# TMC2130.net
KiCad netlist of a schematic drawn in Altium Designer
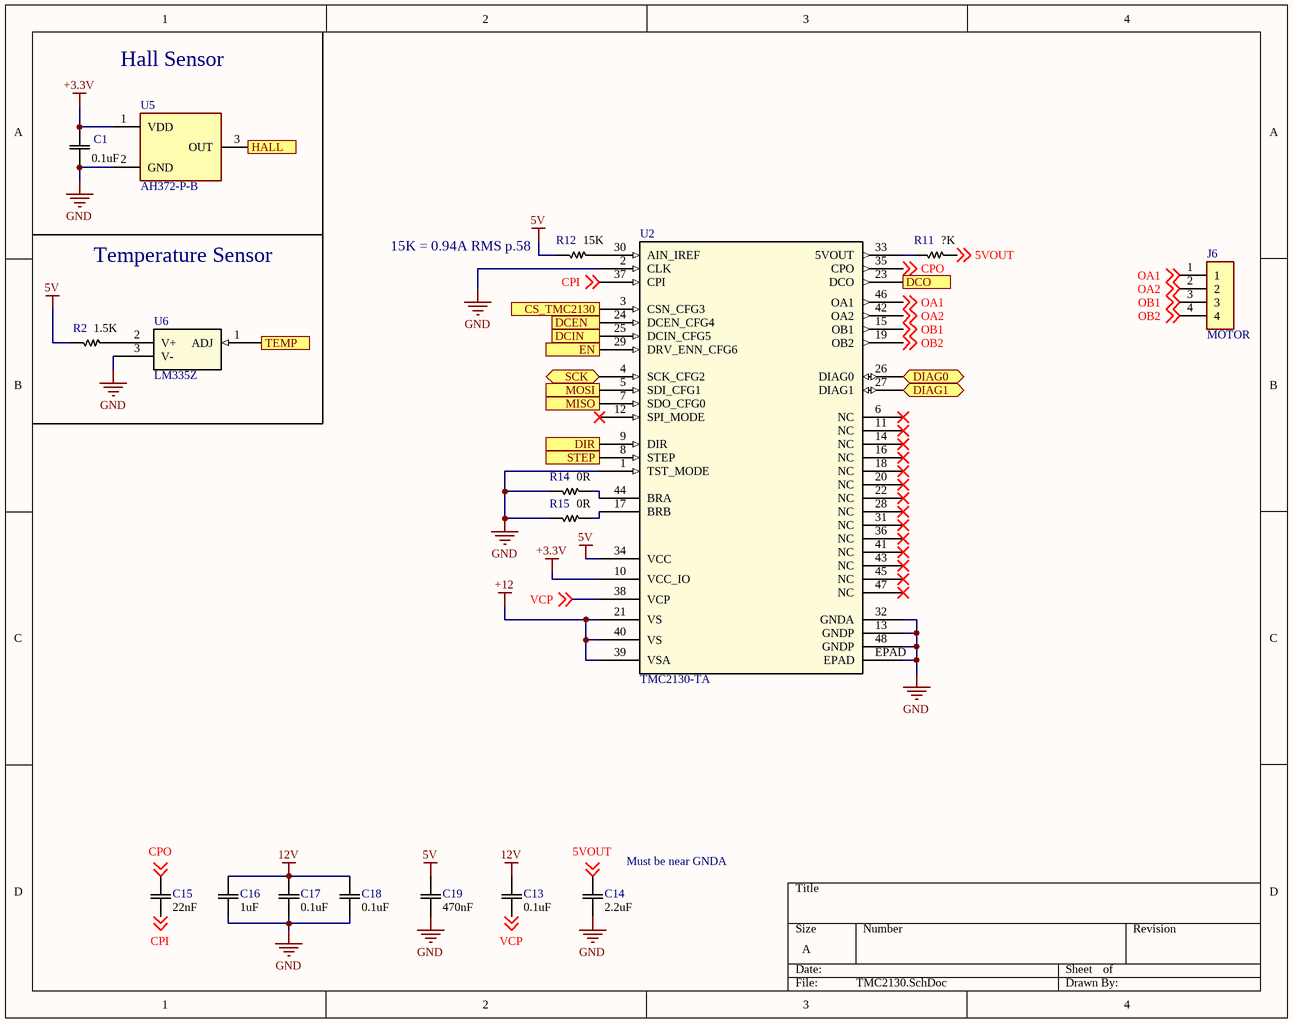
[diagram p0: TMC2130.SchDoc]

(export (version "E")
  (design (tool "Eeschema 10.0.6"))
  (components
    (comp (ref "C1")
      (value "0.1uF")
      (footprint "0603")
      (description "Capacitor SMD 1206")
      (fields
        (field (name "MANUFACTURER_PART_NUMBER") "12065A820JAT2A")
        (field (name "Comment") "Capacitor 1206")
        (field (name "COPYRIGHT") "Copyright (C) 2018 Accelerated Designs. All rights reserved")
      )
      (libsource (lib "Schematic_Emile") (part "Capacitor 1206"))
    )
    (comp (ref "C13")
      (value "0.1uF")
      (footprint "0603")
      (description "Capacitor SMD 1206")
      (fields
        (field (name "MANUFACTURER_PART_NUMBER") "12065A820JAT2A")
        (field (name "Comment") "Capacitor 1206")
        (field (name "COPYRIGHT") "Copyright (C) 2018 Accelerated Designs. All rights reserved")
      )
      (libsource (lib "Schematic_Emile") (part "Capacitor 1206"))
    )
    (comp (ref "C14")
      (value "2.2uF")
      (footprint "0603")
      (description "Capacitor SMD 1206")
      (fields
        (field (name "MANUFACTURER_PART_NUMBER") "12065A820JAT2A")
        (field (name "Comment") "Capacitor 1206")
        (field (name "COPYRIGHT") "Copyright (C) 2018 Accelerated Designs. All rights reserved")
      )
      (libsource (lib "Schematic_Emile") (part "Capacitor 1206"))
    )
    (comp (ref "C15")
      (value "22nF")
      (footprint "0603")
      (description "Capacitor SMD 1206")
      (fields
        (field (name "MANUFACTURER_PART_NUMBER") "12065A820JAT2A")
        (field (name "Comment") "Capacitor 1206")
        (field (name "COPYRIGHT") "Copyright (C) 2018 Accelerated Designs. All rights reserved")
      )
      (libsource (lib "Schematic_Emile") (part "Capacitor 1206"))
    )
    (comp (ref "C16")
      (value "1uF")
      (footprint "0603")
      (description "Capacitor SMD 1206")
      (fields
        (field (name "MANUFACTURER_PART_NUMBER") "12065A820JAT2A")
        (field (name "Comment") "Capacitor 1206")
        (field (name "COPYRIGHT") "Copyright (C) 2018 Accelerated Designs. All rights reserved")
      )
      (libsource (lib "Schematic_Emile") (part "Capacitor 1206"))
    )
    (comp (ref "C17")
      (value "0.1uF")
      (footprint "0603")
      (description "Capacitor SMD 1206")
      (fields
        (field (name "MANUFACTURER_PART_NUMBER") "12065A820JAT2A")
        (field (name "Comment") "Capacitor 1206")
        (field (name "COPYRIGHT") "Copyright (C) 2018 Accelerated Designs. All rights reserved")
      )
      (libsource (lib "Schematic_Emile") (part "Capacitor 1206"))
    )
    (comp (ref "C18")
      (value "0.1uF")
      (footprint "0603")
      (description "Capacitor SMD 1206")
      (fields
        (field (name "MANUFACTURER_PART_NUMBER") "12065A820JAT2A")
        (field (name "Comment") "Capacitor 1206")
        (field (name "COPYRIGHT") "Copyright (C) 2018 Accelerated Designs. All rights reserved")
      )
      (libsource (lib "Schematic_Emile") (part "Capacitor 1206"))
    )
    (comp (ref "C19")
      (value "470nF")
      (footprint "0603")
      (description "Capacitor SMD 1206")
      (fields
        (field (name "MANUFACTURER_PART_NUMBER") "12065A820JAT2A")
        (field (name "Comment") "Capacitor 1206")
        (field (name "COPYRIGHT") "Copyright (C) 2018 Accelerated Designs. All rights reserved")
      )
      (libsource (lib "Schematic_Emile") (part "Capacitor 1206"))
    )
    (comp (ref "J6")
      (value "MOTOR")
      (footprint "JST 4POS 2.5mm 90°")
      (description "Connector")
      (fields
        (field (name "MANUFACTURER_PART_NUMBER") "S4B-XH-A(LF)(SN)")
        (field (name "RS PART NUMBER") "8201589P")
      )
      (libsource (lib "Schematic_Emile") (part "JST 4POS"))
    )
    (comp (ref "R2")
      (value "1.5K")
      (footprint "0603")
      (description "Resistor 1206 SMD")
      (fields
        (field (name "MANUFACTURER_PART_NUMBER") "ERJ8CWFR024V")
        (field (name "Comment") "Resistor 1206")
        (field (name "COPYRIGHT") "Copyright (C) 2018 Accelerated Designs. All rights reserved")
      )
      (libsource (lib "Schematic_Emile") (part "Resistor 1206"))
    )
    (comp (ref "R11")
      (value "?K")
      (footprint "0603")
      (description "Resistor 0603 SMD")
      (fields
        (field (name "MANUFACTURER_PART_NUMBER") "ERJ8CWFR024V")
        (field (name "Comment") "Resistor 0603")
        (field (name "COPYRIGHT") "Copyright (C) 2018 Accelerated Designs. All rights reserved")
      )
      (libsource (lib "Schematic_Emile") (part "Resistor 1206"))
    )
    (comp (ref "R12")
      (value "15K")
      (footprint "0603")
      (description "Resistor 0603 SMD")
      (fields
        (field (name "MANUFACTURER_PART_NUMBER") "ERJ8CWFR024V")
        (field (name "Comment") "Resistor 0603")
        (field (name "COPYRIGHT") "Copyright (C) 2018 Accelerated Designs. All rights reserved")
      )
      (libsource (lib "Schematic_Emile") (part "Resistor 1206"))
    )
    (comp (ref "R14")
      (value "0R")
      (footprint "0603")
      (description "Resistor 0603 SMD")
      (fields
        (field (name "MANUFACTURER_PART_NUMBER") "ERJ8CWFR024V")
        (field (name "Comment") "Resistor 0603")
        (field (name "COPYRIGHT") "Copyright (C) 2018 Accelerated Designs. All rights reserved")
      )
      (libsource (lib "Schematic_Emile") (part "Resistor 1206"))
    )
    (comp (ref "R15")
      (value "0R")
      (footprint "0603")
      (description "Resistor 0603 SMD")
      (fields
        (field (name "MANUFACTURER_PART_NUMBER") "ERJ8CWFR024V")
        (field (name "Comment") "Resistor 0603")
        (field (name "COPYRIGHT") "Copyright (C) 2018 Accelerated Designs. All rights reserved")
      )
      (libsource (lib "Schematic_Emile") (part "Resistor 1206"))
    )
    (comp (ref "U2")
      (value "TMC2130-TA")
      (footprint "eTQFP48_9x9")
      (description "Motor Driver TMC2130")
      (fields (field (name "COPYRIGHT") "Copyright (C) 2016 Accelerated Designs. All rights reserved"))
      (libsource (lib "Schematic_Emile") (part "TMC2130-TA"))
    )
    (comp (ref "U5")
      (value "AH372-P-B")
      (footprint "SamacSys:AH372PB")
      (description "Hall Sensor")
      (fields (field (name "MOUSER PART NUMBER") "621-AH372-P-B") (field (name "RS PART NUMBER") "1333361P"))
      (libsource (lib "Schematic_Emile") (part "AH372-P-B"))
    )
    (comp (ref "U6")
      (value "LM335Z")
      (footprint "TO92")
      (description "Temperature Sensor")
      (fields (field (name "COPYRIGHT") "Copyright (C) 2018 Accelerated Designs. All rights reserved"))
      (libsource (lib "Schematic_Emile") (part "LM335Z"))
    )
  )
  (nets
    (net (code "1") (name "+3.3V") (class "Default")
      (node (ref "C1") (pin "2") (pinfunction "2_2") (pintype "passive"))
      (node (ref "U2") (pin "10") (pinfunction "VCC_IO_10") (pintype "power_in"))
      (node (ref "U5") (pin "1") (pinfunction "VDD_1") (pintype "passive"))
    )
    (net (code "2") (name "+12") (class "Default")
      (node (ref "U2") (pin "21") (pinfunction "VS_21") (pintype "power_in"))
      (node (ref "U2") (pin "39") (pinfunction "VSA_39") (pintype "power_in"))
      (node (ref "U2") (pin "40") (pinfunction "VS_40") (pintype "power_in"))
    )
    (net (code "3") (name "/CS_TMC2130") (class "Default")
      (node (ref "U2") (pin "3") (pinfunction "CSN_CFG3_3") (pintype "input"))
    )
    (net (code "4") (name "/DCEN") (class "Default")
      (node (ref "U2") (pin "24") (pinfunction "DCEN_CFG4_24") (pintype "input"))
    )
    (net (code "5") (name "/DCIN") (class "Default")
      (node (ref "U2") (pin "25") (pinfunction "DCIN_CFG5_25") (pintype "input"))
    )
    (net (code "6") (name "/DCO") (class "Default")
      (node (ref "U2") (pin "23") (pinfunction "DCO_23") (pintype "output"))
    )
    (net (code "7") (name "/DIAG0") (class "Default")
      (node (ref "U2") (pin "26") (pinfunction "DIAG0_26") (pintype "bidirectional"))
    )
    (net (code "8") (name "/DIAG1") (class "Default")
      (node (ref "U2") (pin "27") (pinfunction "DIAG1_27") (pintype "bidirectional"))
    )
    (net (code "9") (name "/DIR") (class "Default")
      (node (ref "U2") (pin "9") (pinfunction "DIR_9") (pintype "input"))
    )
    (net (code "10") (name "/EN") (class "Default")
      (node (ref "U2") (pin "29") (pinfunction "DRV_ENN_CFG6_29") (pintype "input"))
    )
    (net (code "11") (name "/HALL") (class "Default")
      (node (ref "U5") (pin "3") (pinfunction "OUT_3") (pintype "passive"))
    )
    (net (code "12") (name "/MISO") (class "Default")
      (node (ref "U2") (pin "7") (pinfunction "SDO_CFG0_7") (pintype "input"))
    )
    (net (code "13") (name "/MOSI") (class "Default")
      (node (ref "U2") (pin "5") (pinfunction "SDI_CFG1_5") (pintype "input"))
    )
    (net (code "14") (name "/SCK") (class "Default")
      (node (ref "U2") (pin "4") (pinfunction "SCK_CFG2_4") (pintype "input"))
    )
    (net (code "15") (name "/STEP") (class "Default")
      (node (ref "U2") (pin "8") (pinfunction "STEP_8") (pintype "input"))
    )
    (net (code "16") (name "/TEMP") (class "Default")
      (node (ref "U6") (pin "1") (pinfunction "ADJ_1") (pintype "input"))
    )
    (net (code "17") (name "5V") (class "Default")
      (node (ref "C19") (pin "2") (pinfunction "2_2") (pintype "passive"))
      (node (ref "R12") (pin "1") (pinfunction "1_1") (pintype "passive"))
      (node (ref "R2") (pin "1") (pinfunction "1_1") (pintype "passive"))
      (node (ref "U2") (pin "34") (pinfunction "VCC_34") (pintype "power_in"))
    )
    (net (code "18") (name "5VOUT") (class "Default")
      (node (ref "C14") (pin "2") (pinfunction "2_2") (pintype "passive"))
      (node (ref "R11") (pin "2") (pinfunction "2_2") (pintype "passive"))
    )
    (net (code "19") (name "12V") (class "Default")
      (node (ref "C13") (pin "2") (pinfunction "2_2") (pintype "passive"))
      (node (ref "C16") (pin "2") (pinfunction "2_2") (pintype "passive"))
      (node (ref "C17") (pin "2") (pinfunction "2_2") (pintype "passive"))
      (node (ref "C18") (pin "2") (pinfunction "2_2") (pintype "passive"))
    )
    (net (code "20") (name "CPI") (class "Default")
      (node (ref "C15") (pin "1") (pinfunction "1_1") (pintype "passive"))
      (node (ref "U2") (pin "37") (pinfunction "CPI_37") (pintype "input"))
    )
    (net (code "21") (name "CPO") (class "Default")
      (node (ref "C15") (pin "2") (pinfunction "2_2") (pintype "passive"))
      (node (ref "U2") (pin "35") (pinfunction "CPO_35") (pintype "output"))
    )
    (net (code "22") (name "GND") (class "Default")
      (node (ref "C1") (pin "1") (pinfunction "1_1") (pintype "passive"))
      (node (ref "C14") (pin "1") (pinfunction "1_1") (pintype "passive"))
      (node (ref "C16") (pin "1") (pinfunction "1_1") (pintype "passive"))
      (node (ref "C17") (pin "1") (pinfunction "1_1") (pintype "passive"))
      (node (ref "C18") (pin "1") (pinfunction "1_1") (pintype "passive"))
      (node (ref "C19") (pin "1") (pinfunction "1_1") (pintype "passive"))
      (node (ref "R14") (pin "1") (pinfunction "1_1") (pintype "passive"))
      (node (ref "R15") (pin "1") (pinfunction "1_1") (pintype "passive"))
      (node (ref "U2") (pin "1") (pinfunction "TST_MODE_1") (pintype "input"))
      (node (ref "U2") (pin "13") (pinfunction "GNDP_13") (pintype "power_in"))
      (node (ref "U2") (pin "2") (pinfunction "CLK_2") (pintype "input"))
      (node (ref "U2") (pin "32") (pinfunction "GNDA_32") (pintype "power_in"))
      (node (ref "U2") (pin "48") (pinfunction "GNDP_48") (pintype "power_in"))
      (node (ref "U2") (pin "EPAD") (pinfunction "EPAD_EPAD") (pintype "passive"))
      (node (ref "U5") (pin "2") (pinfunction "GND_2") (pintype "passive"))
      (node (ref "U6") (pin "3") (pinfunction "V-_3") (pintype "power_in"))
    )
    (net (code "23") (name "Net-(U2-5VOUT)") (class "Default")
      (node (ref "R11") (pin "1") (pinfunction "1_1") (pintype "passive"))
      (node (ref "U2") (pin "33") (pinfunction "5VOUT_33") (pintype "output"))
    )
    (net (code "24") (name "Net-(U2-AIN_IREF)") (class "Default")
      (node (ref "R12") (pin "2") (pinfunction "2_2") (pintype "passive"))
      (node (ref "U2") (pin "30") (pinfunction "AIN_IREF_30") (pintype "input"))
    )
    (net (code "25") (name "Net-(U2-BRA)") (class "Default")
      (node (ref "R14") (pin "2") (pinfunction "2_2") (pintype "passive"))
      (node (ref "U2") (pin "44") (pinfunction "BRA_44") (pintype "passive"))
    )
    (net (code "26") (name "Net-(U2-BRB)") (class "Default")
      (node (ref "R15") (pin "2") (pinfunction "2_2") (pintype "passive"))
      (node (ref "U2") (pin "17") (pinfunction "BRB_17") (pintype "passive"))
    )
    (net (code "27") (name "Net-(U6-V+)") (class "Default")
      (node (ref "R2") (pin "2") (pinfunction "2_2") (pintype "passive"))
      (node (ref "U6") (pin "2") (pinfunction "V+_2") (pintype "power_in"))
    )
    (net (code "28") (name "OA1") (class "Default")
      (node (ref "J6") (pin "1") (pinfunction "1_1") (pintype "passive"))
      (node (ref "U2") (pin "46") (pinfunction "OA1_46") (pintype "output"))
    )
    (net (code "29") (name "OA2") (class "Default")
      (node (ref "J6") (pin "2") (pinfunction "2_2") (pintype "passive"))
      (node (ref "U2") (pin "42") (pinfunction "OA2_42") (pintype "output"))
    )
    (net (code "30") (name "OB1") (class "Default")
      (node (ref "J6") (pin "3") (pinfunction "3_3") (pintype "passive"))
      (node (ref "U2") (pin "15") (pinfunction "OB1_15") (pintype "output"))
    )
    (net (code "31") (name "OB2") (class "Default")
      (node (ref "J6") (pin "4") (pinfunction "4_4") (pintype "passive"))
      (node (ref "U2") (pin "19") (pinfunction "OB2_19") (pintype "output"))
    )
    (net (code "32") (name "VCP") (class "Default")
      (node (ref "C13") (pin "1") (pinfunction "1_1") (pintype "passive"))
      (node (ref "U2") (pin "38") (pinfunction "VCP_38") (pintype "power_in"))
    )
    (net (code "33") (name "unconnected-(U2-NC-Pad6)") (class "Default")
      (node (ref "U2") (pin "6") (pinfunction "NC_6") (pintype "passive+no_connect"))
    )
    (net (code "34") (name "unconnected-(U2-NC-Pad11)") (class "Default")
      (node (ref "U2") (pin "11") (pinfunction "NC_11") (pintype "passive+no_connect"))
    )
    (net (code "35") (name "unconnected-(U2-NC-Pad14)") (class "Default")
      (node (ref "U2") (pin "14") (pinfunction "NC_14") (pintype "passive+no_connect"))
    )
    (net (code "36") (name "unconnected-(U2-NC-Pad16)") (class "Default")
      (node (ref "U2") (pin "16") (pinfunction "NC_16") (pintype "passive+no_connect"))
    )
    (net (code "37") (name "unconnected-(U2-NC-Pad18)") (class "Default")
      (node (ref "U2") (pin "18") (pinfunction "NC_18") (pintype "passive+no_connect"))
    )
    (net (code "38") (name "unconnected-(U2-NC-Pad20)") (class "Default")
      (node (ref "U2") (pin "20") (pinfunction "NC_20") (pintype "passive+no_connect"))
    )
    (net (code "39") (name "unconnected-(U2-NC-Pad22)") (class "Default")
      (node (ref "U2") (pin "22") (pinfunction "NC_22") (pintype "passive+no_connect"))
    )
    (net (code "40") (name "unconnected-(U2-NC-Pad28)") (class "Default")
      (node (ref "U2") (pin "28") (pinfunction "NC_28") (pintype "passive+no_connect"))
    )
    (net (code "41") (name "unconnected-(U2-NC-Pad31)") (class "Default")
      (node (ref "U2") (pin "31") (pinfunction "NC_31") (pintype "passive+no_connect"))
    )
    (net (code "42") (name "unconnected-(U2-NC-Pad36)") (class "Default")
      (node (ref "U2") (pin "36") (pinfunction "NC_36") (pintype "passive+no_connect"))
    )
    (net (code "43") (name "unconnected-(U2-NC-Pad41)") (class "Default")
      (node (ref "U2") (pin "41") (pinfunction "NC_41") (pintype "passive+no_connect"))
    )
    (net (code "44") (name "unconnected-(U2-NC-Pad43)") (class "Default")
      (node (ref "U2") (pin "43") (pinfunction "NC_43") (pintype "passive+no_connect"))
    )
    (net (code "45") (name "unconnected-(U2-NC-Pad45)") (class "Default")
      (node (ref "U2") (pin "45") (pinfunction "NC_45") (pintype "passive+no_connect"))
    )
    (net (code "46") (name "unconnected-(U2-NC-Pad47)") (class "Default")
      (node (ref "U2") (pin "47") (pinfunction "NC_47") (pintype "passive+no_connect"))
    )
    (net (code "47") (name "unconnected-(U2-SPI_MODE-Pad12)") (class "Default")
      (node (ref "U2") (pin "12") (pinfunction "SPI_MODE_12") (pintype "input+no_connect"))
    )
  )
)
